# Tilt-PIC12F635.net
KiCad netlist of a schematic drawn in EAGLE
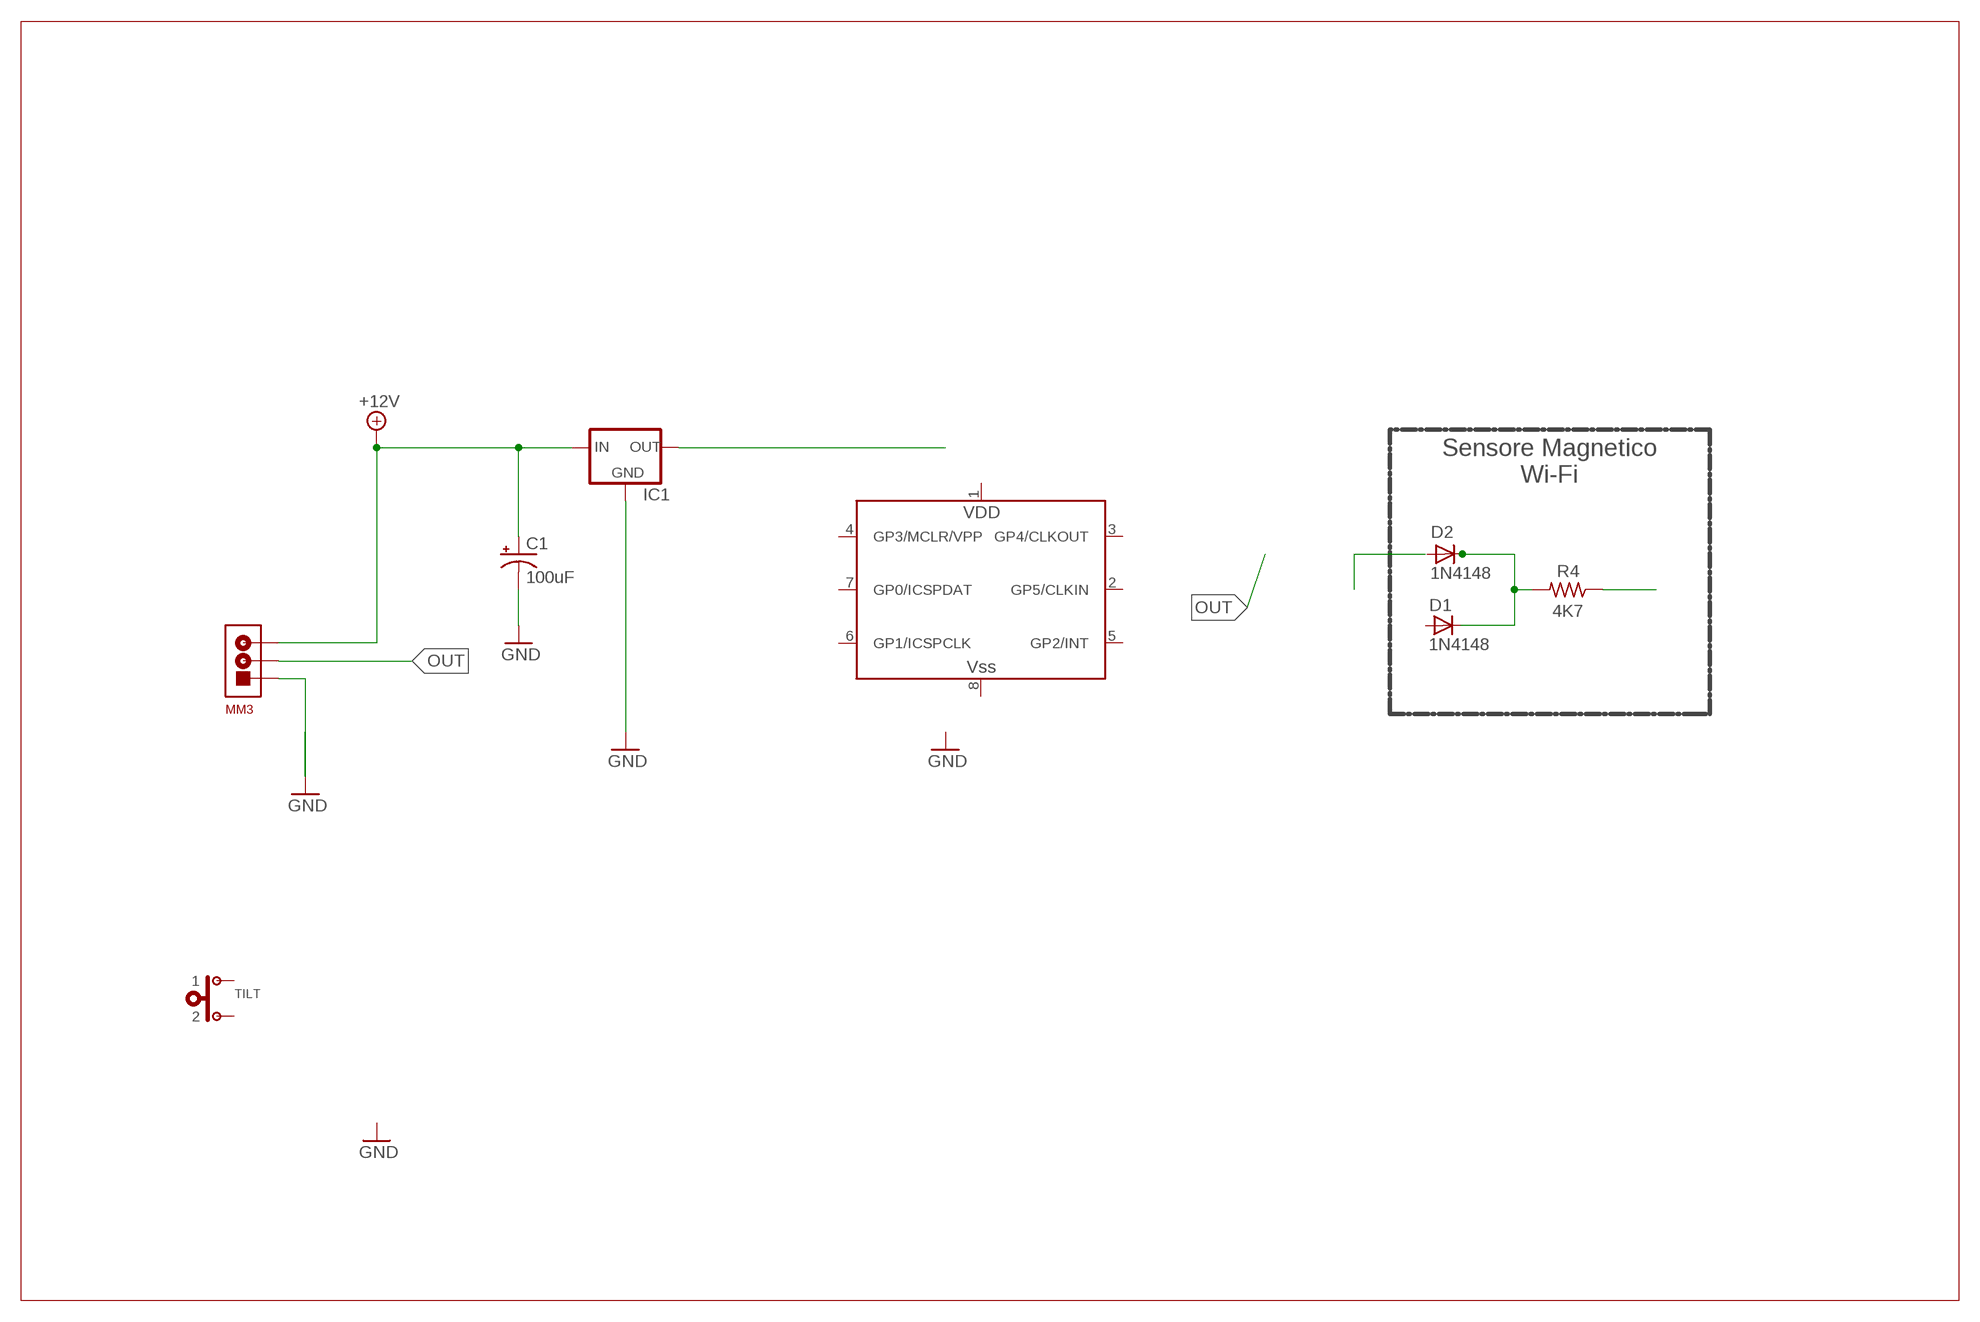
[diagram p0: schematic, sheet 1]

(export (version "E")
  (design (tool "Eeschema 10.0.6"))
  (components
    (comp (ref "C1")
      (value "100uF")
      (footprint "eagle-import:085CS_1AR")
      (libsource (lib "eagle-import") (part "CPOL-US085CS-1AR"))
    )
    (comp (ref "D1")
      (value "1N4148")
      (footprint "eagle-import:DO35-10")
      (libsource (lib "eagle-import") (part "1N4148DO35-10"))
    )
    (comp (ref "D2")
      (value "1N4148")
      (footprint "eagle-import:DO35-10")
      (libsource (lib "eagle-import") (part "1N4148DO35-10"))
    )
    (comp (ref "IC1")
      (value "78LXX")
      (footprint "eagle-import:78LXX")
      (libsource (lib "eagle-import") (part "78LXX"))
    )
    (comp (ref "MM3")
      (value "MAMMUTH03")
      (footprint "eagle-import:MAMMUTH03")
      (libsource (lib "eagle-import") (part "MAMMUTH03"))
    )
    (comp (ref "R4")
      (value "4K7")
      (footprint "eagle-import:0207_12")
      (libsource (lib "eagle-import") (part "R-US_0207/12"))
    )
    (comp (ref "TILT")
      (value "PULSANTENO")
      (footprint "eagle-import:SIP02")
      (libsource (lib "eagle-import") (part "PULSANTENO"))
    )
    (comp (ref "U$1")
      (value "PIC12F635")
      (footprint "eagle-import:DIL8")
      (libsource (lib "eagle-import") (part "PIC12F635"))
    )
  )
  (nets
    (net (code "1") (name "+12V") (class "Default")
      (node (ref "C1") (pin "+") (pinfunction "+_+") (pintype "passive"))
      (node (ref "IC1") (pin "IN") (pinfunction "IN_IN") (pintype "input"))
      (node (ref "MM3") (pin "P$3") (pinfunction "3_P$3") (pintype "bidirectional"))
    )
    (net (code "2") (name "/VDD") (class "Default")
      (node (ref "U$1") (pin "1") (pinfunction "VDD_1") (pintype "power_in"))
    )
    (net (code "3") (name "/VSS") (class "Default")
      (node (ref "U$1") (pin "8") (pinfunction "VSS_8") (pintype "power_in"))
    )
    (net (code "4") (name "GND") (class "Default")
      (node (ref "C1") (pin "-") (pinfunction "-_-") (pintype "passive"))
      (node (ref "IC1") (pin "GND") (pinfunction "GND_GND") (pintype "input"))
      (node (ref "MM3") (pin "P$1") (pinfunction "1_P$1") (pintype "bidirectional"))
    )
    (net (code "5") (name "Net-(D1-PadC)") (class "Default")
      (node (ref "D1") (pin "C") (pinfunction "C_C") (pintype "passive"))
      (node (ref "D2") (pin "C") (pinfunction "C_C") (pintype "passive"))
      (node (ref "R4") (pin "2") (pinfunction "2_2") (pintype "passive"))
    )
    (net (code "6") (name "OUT") (class "Default")
      (node (ref "MM3") (pin "P$2") (pinfunction "2_P$2") (pintype "bidirectional"))
    )
    (net (code "7") (name "unconnected-(D1-PadA)") (class "Default")
      (node (ref "D1") (pin "A") (pinfunction "A_A") (pintype "passive"))
    )
    (net (code "8") (name "unconnected-(D2-PadA)") (class "Default")
      (node (ref "D2") (pin "A") (pinfunction "A_A") (pintype "passive"))
    )
    (net (code "9") (name "unconnected-(IC1-PadOUT)") (class "Default")
      (node (ref "IC1") (pin "OUT") (pinfunction "OUT_OUT") (pintype "passive"))
    )
    (net (code "10") (name "unconnected-(R4-Pad1)") (class "Default")
      (node (ref "R4") (pin "1") (pinfunction "1_1") (pintype "passive"))
    )
    (net (code "11") (name "unconnected-(TILT-Pad1)") (class "Default")
      (node (ref "TILT") (pin "1") (pinfunction "1_1") (pintype "bidirectional"))
    )
    (net (code "12") (name "unconnected-(TILT-Pad2)") (class "Default")
      (node (ref "TILT") (pin "2") (pinfunction "2_2") (pintype "bidirectional"))
    )
    (net (code "13") (name "unconnected-(U$1-GP0{slash}ICSPDAT-Pad7)") (class "Default")
      (node (ref "U$1") (pin "7") (pinfunction "GP0/ICSPDAT_7") (pintype "bidirectional"))
    )
    (net (code "14") (name "unconnected-(U$1-GP1{slash}ICSPCLK-Pad6)") (class "Default")
      (node (ref "U$1") (pin "6") (pinfunction "GP1/ICSPCLK_6") (pintype "bidirectional"))
    )
    (net (code "15") (name "unconnected-(U$1-GP2{slash}INT-Pad5)") (class "Default")
      (node (ref "U$1") (pin "5") (pinfunction "GP2/INT_5") (pintype "bidirectional"))
    )
    (net (code "16") (name "unconnected-(U$1-GP3{slash}MCLR{slash}VPP-Pad4)") (class "Default")
      (node (ref "U$1") (pin "4") (pinfunction "GP3/MCLR/VPP_4") (pintype "bidirectional"))
    )
    (net (code "17") (name "unconnected-(U$1-GP4{slash}CLKOUT-Pad3)") (class "Default")
      (node (ref "U$1") (pin "3") (pinfunction "GP4/CLKOUT_3") (pintype "bidirectional"))
    )
    (net (code "18") (name "unconnected-(U$1-GP5{slash}CLKIN-Pad2)") (class "Default")
      (node (ref "U$1") (pin "2") (pinfunction "GP5/CLKIN_2") (pintype "bidirectional"))
    )
  )
)
